# Sheet04.net
KiCad netlist of a schematic drawn in Altium Designer
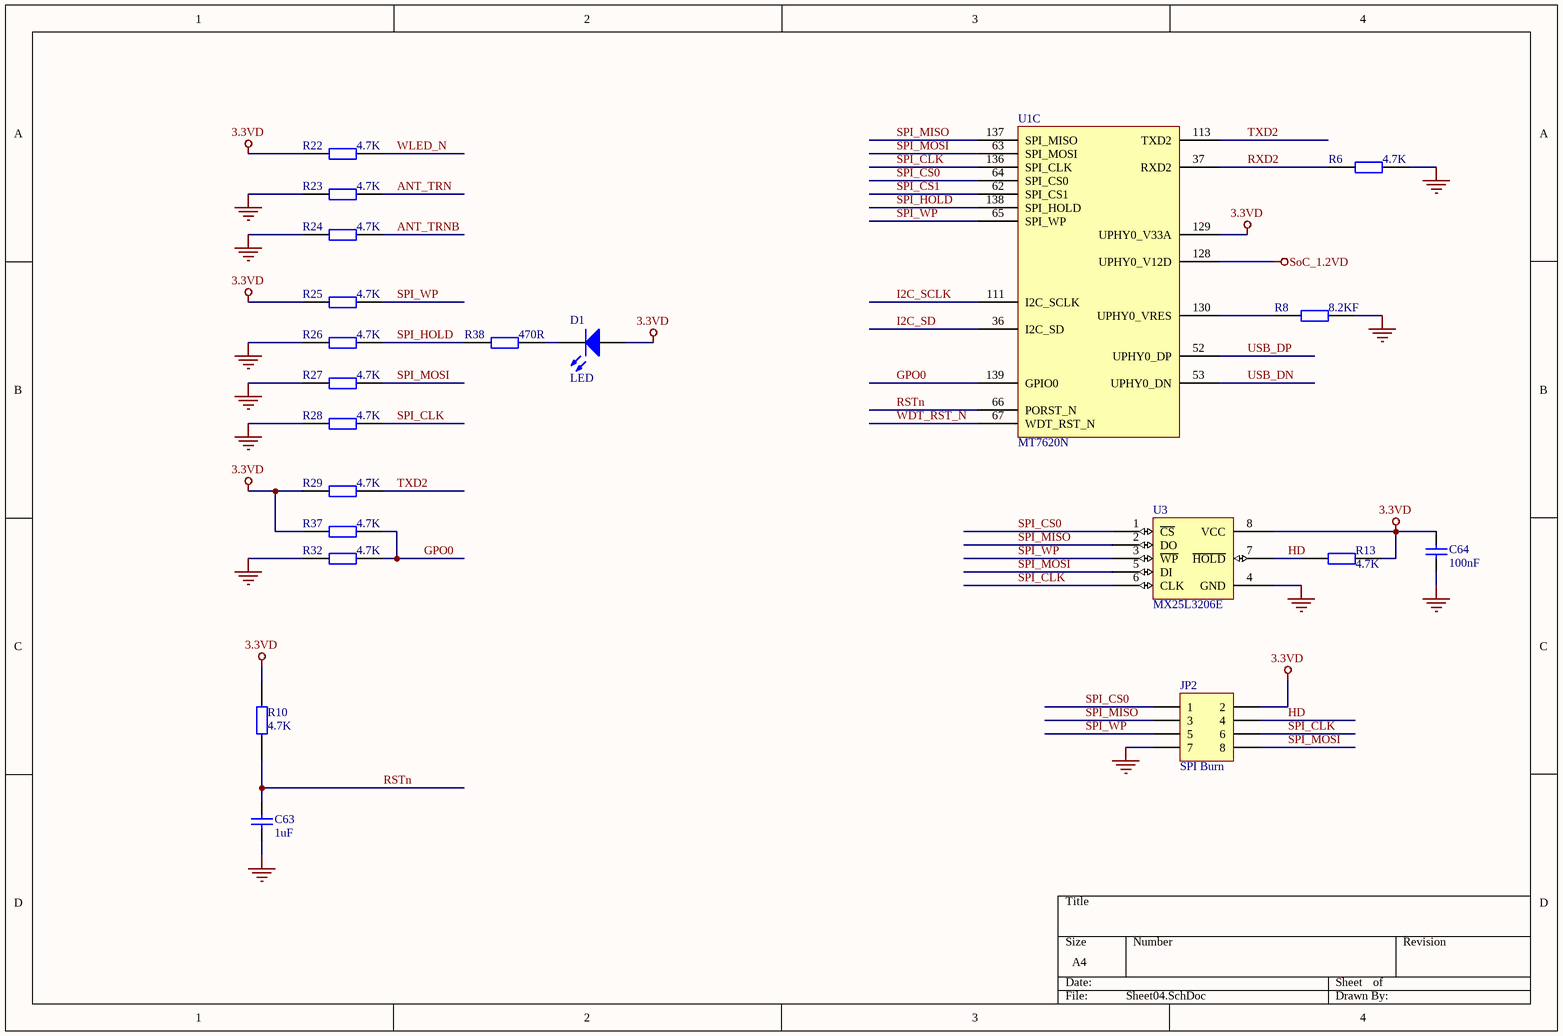
[diagram p0: Sheet04.SchDoc]

(export (version "E")
  (design (tool "Eeschema 10.0.6"))
  (components
    (comp (ref "C63")
      (value "1uF")
      (footprint "R0402")
      (description "2pF, 50V, +/-0.25pF")
      (fields
        (field (name "MANUFACTURER") "Generic Components")
        (field (name "PUBLISHER") "Altium Hobart Technology Centre")
      )
      (libsource (lib "myschlib") (part "Cap Semi"))
    )
    (comp (ref "C64")
      (value "100nF")
      (footprint "R0402")
      (description "2pF, 50V, +/-0.25pF")
      (fields
        (field (name "MANUFACTURER") "Generic Components")
        (field (name "PUBLISHER") "Altium Hobart Technology Centre")
      )
      (libsource (lib "myschlib") (part "Cap Semi"))
    )
    (comp (ref "D1") (value "LED") (footprint "D0603") (libsource (lib "myschlib") (part "LED")))
    (comp (ref "JP2")
      (value "SPI Burn")
      (footprint "IDC-2X4-2_54_M")
      (description "Header, 4-Pin, Dual row")
      (fields (field (name "PUBLISHER") "Altium Limited"))
      (libsource (lib "Miscellaneous Connectors") (part "Header 4X2"))
    )
    (comp (ref "R6") (value "4.7K") (footprint "R0402") (libsource (lib "myschlib") (part "RES")))
    (comp (ref "R8") (value "8.2KF") (footprint "R0402") (libsource (lib "myschlib") (part "RES")))
    (comp (ref "R10") (value "4.7K") (footprint "R0402") (libsource (lib "") (part "RES_1")))
    (comp (ref "R13") (value "4.7K") (footprint "R0402") (libsource (lib "myschlib") (part "RES")))
    (comp (ref "R22") (value "4.7K") (footprint "R0402") (libsource (lib "myschlib") (part "RES")))
    (comp (ref "R23") (value "4.7K") (footprint "R0402") (libsource (lib "myschlib") (part "RES")))
    (comp (ref "R24") (value "4.7K") (footprint "R0402") (libsource (lib "myschlib") (part "RES")))
    (comp (ref "R25") (value "4.7K") (footprint "R0402") (libsource (lib "myschlib") (part "RES")))
    (comp (ref "R26") (value "4.7K") (footprint "R0402") (libsource (lib "myschlib") (part "RES")))
    (comp (ref "R27") (value "4.7K") (footprint "R0402") (libsource (lib "myschlib") (part "RES")))
    (comp (ref "R28") (value "4.7K") (footprint "R0402") (libsource (lib "myschlib") (part "RES")))
    (comp (ref "R29") (value "4.7K") (footprint "R0402") (libsource (lib "myschlib") (part "RES")))
    (comp (ref "R32") (value "4.7K") (footprint "R0402") (libsource (lib "myschlib") (part "RES")))
    (comp (ref "R37") (value "4.7K") (footprint "R0402") (libsource (lib "myschlib") (part "RES")))
    (comp (ref "R38") (value "470R") (footprint "R0402") (libsource (lib "myschlib") (part "RES")))
    (comp (ref "U1") (value "MT7620N") (footprint "QFN-148-RT") (libsource (lib "myschlib") (part "MT7620N")))
    (comp (ref "U3")
      (value "MX25L3206E")
      (footprint "SO-8W")
      (libsource (lib "Schlib_IC") (part "MX25L3205DM2I"))
    )
  )
  (nets
    (net (code "1") (name "/ANT_TRN") (class "Default")
      (node (ref "R23") (pin "1") (pinfunction "1_1") (pintype "passive"))
    )
    (net (code "2") (name "/ANT_TRNB") (class "Default")
      (node (ref "R24") (pin "1") (pinfunction "1_1") (pintype "passive"))
    )
    (net (code "3") (name "/GPO0") (class "Default")
      (node (ref "R32") (pin "1") (pinfunction "1_1") (pintype "passive"))
      (node (ref "R37") (pin "1") (pinfunction "1_1") (pintype "passive"))
      (node (ref "U1") (pin "139") (pinfunction "GPIO0_139") (pintype "passive"))
    )
    (net (code "4") (name "/HD") (class "Default")
      (node (ref "JP2") (pin "4") (pinfunction "4_4") (pintype "passive"))
      (node (ref "R13") (pin "2") (pinfunction "2_2") (pintype "passive"))
      (node (ref "U3") (pin "7") (pinfunction "~{HOLD}_7") (pintype "bidirectional"))
    )
    (net (code "5") (name "/I2C_SCLK") (class "Default")
      (node (ref "U1") (pin "111") (pinfunction "I2C_SCLK_111") (pintype "passive"))
    )
    (net (code "6") (name "/I2C_SD") (class "Default")
      (node (ref "U1") (pin "36") (pinfunction "I2C_SD_36") (pintype "passive"))
    )
    (net (code "7") (name "/RSTn") (class "Default")
      (node (ref "C63") (pin "1") (pinfunction "1_1") (pintype "passive"))
      (node (ref "R10") (pin "2") (pinfunction "2_2") (pintype "passive"))
      (node (ref "U1") (pin "66") (pinfunction "PORST_N_66") (pintype "passive"))
    )
    (net (code "8") (name "/RXD2") (class "Default")
      (node (ref "R6") (pin "2") (pinfunction "2_2") (pintype "passive"))
      (node (ref "U1") (pin "37") (pinfunction "RXD2_37") (pintype "passive"))
    )
    (net (code "9") (name "/SPI_CLK") (class "Default")
      (node (ref "JP2") (pin "6") (pinfunction "6_6") (pintype "passive"))
      (node (ref "R28") (pin "1") (pinfunction "1_1") (pintype "passive"))
      (node (ref "U1") (pin "136") (pinfunction "SPI_CLK_136") (pintype "passive"))
      (node (ref "U3") (pin "6") (pinfunction "CLK_6") (pintype "bidirectional"))
    )
    (net (code "10") (name "/SPI_CS0") (class "Default")
      (node (ref "JP2") (pin "1") (pinfunction "1_1") (pintype "passive"))
      (node (ref "U1") (pin "64") (pinfunction "SPI_CS0_64") (pintype "passive"))
      (node (ref "U3") (pin "1") (pinfunction "~{CS}_1") (pintype "bidirectional"))
    )
    (net (code "11") (name "/SPI_CS1") (class "Default")
      (node (ref "U1") (pin "62") (pinfunction "SPI_CS1_62") (pintype "passive"))
    )
    (net (code "12") (name "/SPI_HOLD") (class "Default")
      (node (ref "R26") (pin "1") (pinfunction "1_1") (pintype "passive"))
      (node (ref "R38") (pin "2") (pinfunction "2_2") (pintype "passive"))
      (node (ref "U1") (pin "138") (pinfunction "SPI_HOLD_138") (pintype "passive"))
    )
    (net (code "13") (name "/SPI_MISO") (class "Default")
      (node (ref "JP2") (pin "3") (pinfunction "3_3") (pintype "passive"))
      (node (ref "U1") (pin "137") (pinfunction "SPI_MISO_137") (pintype "passive"))
      (node (ref "U3") (pin "2") (pinfunction "DO_2") (pintype "bidirectional"))
    )
    (net (code "14") (name "/SPI_MOSI") (class "Default")
      (node (ref "JP2") (pin "8") (pinfunction "8_8") (pintype "passive"))
      (node (ref "R27") (pin "1") (pinfunction "1_1") (pintype "passive"))
      (node (ref "U1") (pin "63") (pinfunction "SPI_MOSI_63") (pintype "passive"))
      (node (ref "U3") (pin "5") (pinfunction "DI_5") (pintype "bidirectional"))
    )
    (net (code "15") (name "/SPI_WP") (class "Default")
      (node (ref "JP2") (pin "5") (pinfunction "5_5") (pintype "passive"))
      (node (ref "R25") (pin "1") (pinfunction "1_1") (pintype "passive"))
      (node (ref "U1") (pin "65") (pinfunction "SPI_WP_65") (pintype "passive"))
      (node (ref "U3") (pin "3") (pinfunction "~{WP}_3") (pintype "bidirectional"))
    )
    (net (code "16") (name "/TXD2") (class "Default")
      (node (ref "R29") (pin "1") (pinfunction "1_1") (pintype "passive"))
      (node (ref "U1") (pin "113") (pinfunction "TXD2_113") (pintype "passive"))
    )
    (net (code "17") (name "/USB_DN") (class "Default")
      (node (ref "U1") (pin "53") (pinfunction "UPHY0_DN_53") (pintype "passive"))
    )
    (net (code "18") (name "/USB_DP") (class "Default")
      (node (ref "U1") (pin "52") (pinfunction "UPHY0_DP_52") (pintype "passive"))
    )
    (net (code "19") (name "/WDT_RST_N") (class "Default")
      (node (ref "U1") (pin "67") (pinfunction "WDT_RST_N_67") (pintype "passive"))
    )
    (net (code "20") (name "/WLED_N") (class "Default")
      (node (ref "R22") (pin "1") (pinfunction "1_1") (pintype "passive"))
    )
    (net (code "21") (name "3.3VD") (class "Default")
      (node (ref "C64") (pin "1") (pinfunction "1_1") (pintype "passive"))
      (node (ref "D1") (pin "1") (pinfunction "A_1") (pintype "passive"))
      (node (ref "JP2") (pin "2") (pinfunction "2_2") (pintype "passive"))
      (node (ref "R10") (pin "1") (pinfunction "1_1") (pintype "passive"))
      (node (ref "R13") (pin "1") (pinfunction "1_1") (pintype "passive"))
      (node (ref "R22") (pin "2") (pinfunction "2_2") (pintype "passive"))
      (node (ref "R25") (pin "2") (pinfunction "2_2") (pintype "passive"))
      (node (ref "R29") (pin "2") (pinfunction "2_2") (pintype "passive"))
      (node (ref "R37") (pin "2") (pinfunction "2_2") (pintype "passive"))
      (node (ref "U1") (pin "129") (pinfunction "UPHY0_V33A_129") (pintype "passive"))
      (node (ref "U3") (pin "8") (pinfunction "VCC_8") (pintype "power_in"))
    )
    (net (code "22") (name "GND") (class "Default")
      (node (ref "C63") (pin "2") (pinfunction "2_2") (pintype "passive"))
      (node (ref "C64") (pin "2") (pinfunction "2_2") (pintype "passive"))
      (node (ref "JP2") (pin "7") (pinfunction "7_7") (pintype "passive"))
      (node (ref "R23") (pin "2") (pinfunction "2_2") (pintype "passive"))
      (node (ref "R24") (pin "2") (pinfunction "2_2") (pintype "passive"))
      (node (ref "R26") (pin "2") (pinfunction "2_2") (pintype "passive"))
      (node (ref "R27") (pin "2") (pinfunction "2_2") (pintype "passive"))
      (node (ref "R28") (pin "2") (pinfunction "2_2") (pintype "passive"))
      (node (ref "R32") (pin "2") (pinfunction "2_2") (pintype "passive"))
      (node (ref "R6") (pin "1") (pinfunction "1_1") (pintype "passive"))
      (node (ref "R8") (pin "1") (pinfunction "1_1") (pintype "passive"))
      (node (ref "U3") (pin "4") (pinfunction "GND_4") (pintype "power_in"))
    )
    (net (code "23") (name "Net-(D1-K)") (class "Default")
      (node (ref "D1") (pin "2") (pinfunction "K_2") (pintype "passive"))
      (node (ref "R38") (pin "1") (pinfunction "1_1") (pintype "passive"))
    )
    (net (code "24") (name "Net-(U1C-UPHY0_VRES)") (class "Default")
      (node (ref "R8") (pin "2") (pinfunction "2_2") (pintype "passive"))
      (node (ref "U1") (pin "130") (pinfunction "UPHY0_VRES_130") (pintype "passive"))
    )
    (net (code "25") (name "SoC_1.2VD") (class "Default")
      (node (ref "U1") (pin "128") (pinfunction "UPHY0_V12D_128") (pintype "passive"))
    )
  )
)
